# 3tastsp_v5_resistorcooldrive_battcheck.net
KiCad netlist of a schematic drawn in EAGLE
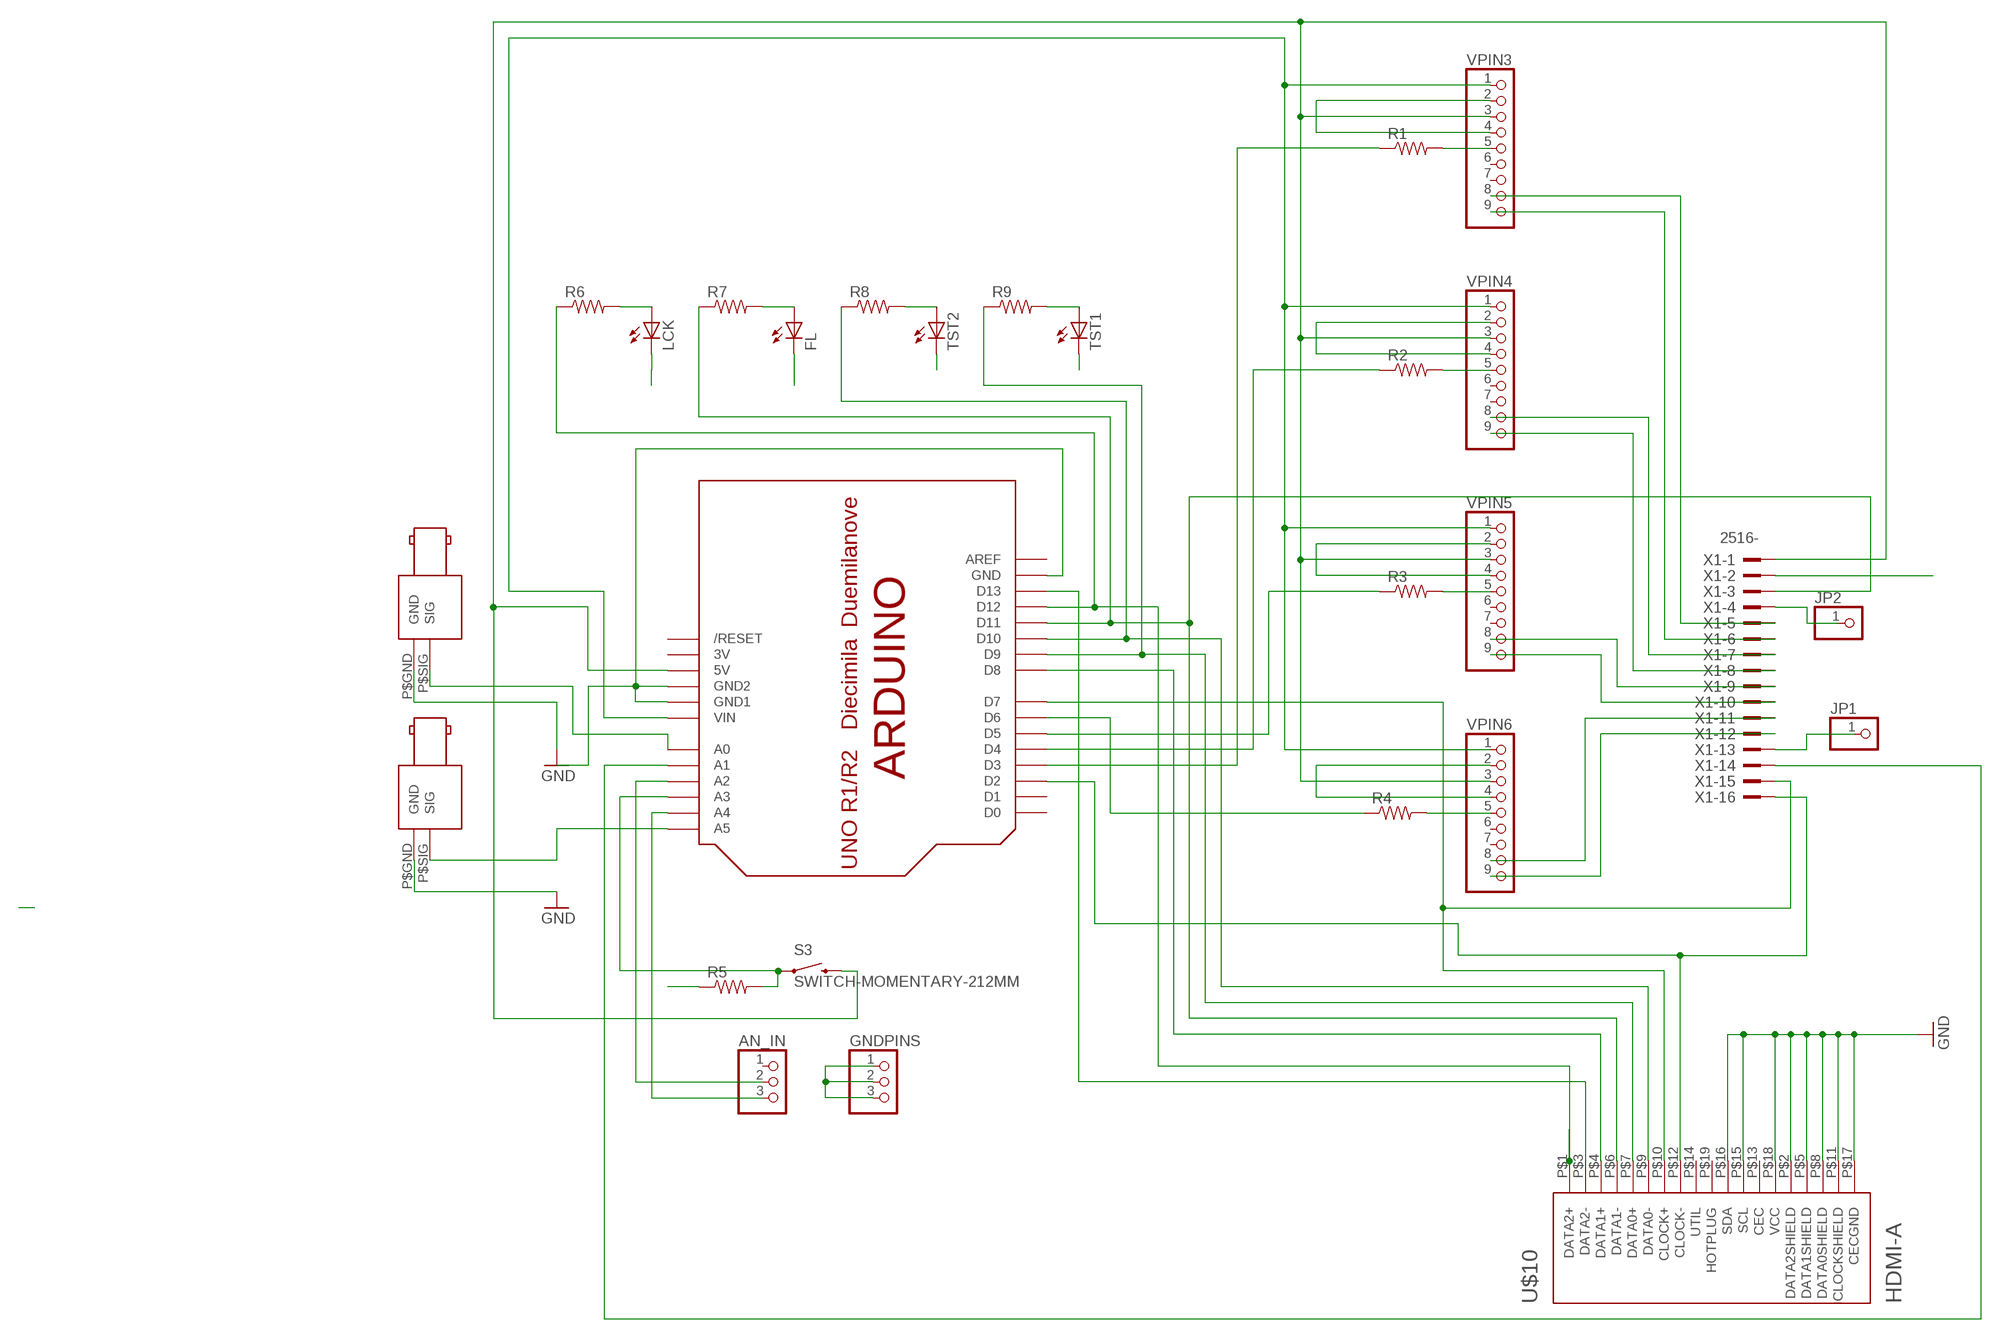
[diagram p0: schematic, sheet 1]

(export (version "E")
  (design (tool "Eeschema 10.0.6"))
  (components
    (comp (ref "AN_IN")
      (value "PINHD-1X3")
      (footprint "eagle-import:1X03")
      (libsource (lib "eagle-import") (part "PINHD-1X3"))
    )
    (comp (ref "FL")
      (value "LED5MM")
      (footprint "eagle-import:LED5MM")
      (libsource (lib "eagle-import") (part "LED5MM"))
    )
    (comp (ref "GNDPINS")
      (value "PINHD-1X3")
      (footprint "eagle-import:1X03")
      (libsource (lib "eagle-import") (part "PINHD-1X3"))
    )
    (comp (ref "JP1")
      (value "PINHD-1X1")
      (footprint "eagle-import:1X01")
      (libsource (lib "eagle-import") (part "PINHD-1X1"))
    )
    (comp (ref "JP2")
      (value "PINHD-1X1")
      (footprint "eagle-import:1X01")
      (libsource (lib "eagle-import") (part "PINHD-1X1"))
    )
    (comp (ref "LCK")
      (value "LED5MM")
      (footprint "eagle-import:LED5MM")
      (libsource (lib "eagle-import") (part "LED5MM"))
    )
    (comp (ref "LICKSIG")
      (value "BNC_RIGHT_ANGLE")
      (footprint "eagle-import:BNC_RIGHT_ANGLE")
      (libsource (lib "eagle-import") (part "BNC_RIGHT_ANGLE"))
    )
    (comp (ref "R1")
      (value "1KOHM-1/4W-1%(PTH)HORIZ-KIT")
      (footprint "eagle-import:AXIAL-0.3EZ")
      (libsource (lib "eagle-import") (part "1KOHM-1/4W-1%(PTH)HORIZ-KIT"))
    )
    (comp (ref "R2")
      (value "1KOHM-1/4W-1%(PTH)HORIZ-KIT")
      (footprint "eagle-import:AXIAL-0.3EZ")
      (libsource (lib "eagle-import") (part "1KOHM-1/4W-1%(PTH)HORIZ-KIT"))
    )
    (comp (ref "R3")
      (value "1KOHM-1/4W-1%(PTH)HORIZ-KIT")
      (footprint "eagle-import:AXIAL-0.3EZ")
      (libsource (lib "eagle-import") (part "1KOHM-1/4W-1%(PTH)HORIZ-KIT"))
    )
    (comp (ref "R4")
      (value "1KOHM-1/4W-1%(PTH)HORIZ-KIT")
      (footprint "eagle-import:AXIAL-0.3EZ")
      (libsource (lib "eagle-import") (part "1KOHM-1/4W-1%(PTH)HORIZ-KIT"))
    )
    (comp (ref "R5")
      (value "1KOHM-1/4W-1%(PTH)HORIZ-KIT")
      (footprint "eagle-import:AXIAL-0.3EZ")
      (libsource (lib "eagle-import") (part "1KOHM-1/4W-1%(PTH)HORIZ-KIT"))
    )
    (comp (ref "R6")
      (value "1KOHM-1/4W-1%(PTH)HORIZ-KIT")
      (footprint "eagle-import:AXIAL-0.3EZ")
      (libsource (lib "eagle-import") (part "1KOHM-1/4W-1%(PTH)HORIZ-KIT"))
    )
    (comp (ref "R7")
      (value "1KOHM-1/4W-1%(PTH)HORIZ-KIT")
      (footprint "eagle-import:AXIAL-0.3EZ")
      (libsource (lib "eagle-import") (part "1KOHM-1/4W-1%(PTH)HORIZ-KIT"))
    )
    (comp (ref "R8")
      (value "1KOHM-1/4W-1%(PTH)HORIZ-KIT")
      (footprint "eagle-import:AXIAL-0.3EZ")
      (libsource (lib "eagle-import") (part "1KOHM-1/4W-1%(PTH)HORIZ-KIT"))
    )
    (comp (ref "R9")
      (value "1KOHM-1/4W-1%(PTH)HORIZ-KIT")
      (footprint "eagle-import:AXIAL-0.3EZ")
      (libsource (lib "eagle-import") (part "1KOHM-1/4W-1%(PTH)HORIZ-KIT"))
    )
    (comp (ref "S3")
      (value "SWITCH-MOMENTARY-212MM")
      (footprint "eagle-import:TACTILE-PTH-12MM")
      (libsource (lib "eagle-import") (part "SWITCH-MOMENTARY-212MM"))
    )
    (comp (ref "TRIALSIG")
      (value "BNC_RIGHT_ANGLE")
      (footprint "eagle-import:BNC_RIGHT_ANGLE")
      (libsource (lib "eagle-import") (part "BNC_RIGHT_ANGLE"))
    )
    (comp (ref "TST1")
      (value "LED5MM")
      (footprint "eagle-import:LED5MM")
      (libsource (lib "eagle-import") (part "LED5MM"))
    )
    (comp (ref "TST2")
      (value "LED5MM")
      (footprint "eagle-import:LED5MM")
      (libsource (lib "eagle-import") (part "LED5MM"))
    )
    (comp (ref "U$1")
      (value "ARDUINO-NOHOLE")
      (footprint "eagle-import:ARDUINO-NOHOLE")
      (libsource (lib "eagle-import") (part "ARDUINO-NOHOLE"))
    )
    (comp (ref "U$10")
      (value "HDMI-A")
      (footprint "eagle-import:HDMI_A")
      (libsource (lib "eagle-import") (part "HDMI-A"))
    )
    (comp (ref "VPIN3")
      (value "PINHD-1X9")
      (footprint "eagle-import:1X09")
      (libsource (lib "eagle-import") (part "PINHD-1X9"))
    )
    (comp (ref "VPIN4")
      (value "PINHD-1X9")
      (footprint "eagle-import:1X09")
      (libsource (lib "eagle-import") (part "PINHD-1X9"))
    )
    (comp (ref "VPIN5")
      (value "PINHD-1X9")
      (footprint "eagle-import:1X09")
      (libsource (lib "eagle-import") (part "PINHD-1X9"))
    )
    (comp (ref "VPIN6")
      (value "PINHD-1X9")
      (footprint "eagle-import:1X09")
      (libsource (lib "eagle-import") (part "PINHD-1X9"))
    )
    (comp (ref "X1")
      (value "2516-")
      (footprint "eagle-import:PAK100_2500-16")
      (libsource (lib "eagle-import") (part "2516-"))
    )
  )
  (nets
    (net (code "1") (name "/3V") (class "Default")
      (node (ref "U$1") (pin "3V") (pinfunction "3V_3V") (pintype "power_in"))
    )
    (net (code "2") (name "GND") (class "Default")
      (node (ref "FL") (pin "K") (pinfunction "C_K") (pintype "passive"))
      (node (ref "GNDPINS") (pin "1") (pinfunction "1_1") (pintype "passive"))
      (node (ref "GNDPINS") (pin "2") (pinfunction "2_2") (pintype "passive"))
      (node (ref "GNDPINS") (pin "3") (pinfunction "3_3") (pintype "passive"))
      (node (ref "LCK") (pin "K") (pinfunction "C_K") (pintype "passive"))
      (node (ref "LICKSIG") (pin "P$GND") (pinfunction "GND_P$GND") (pintype "bidirectional"))
      (node (ref "R5") (pin "P$1") (pinfunction "1_P$1") (pintype "passive"))
      (node (ref "TRIALSIG") (pin "P$GND") (pinfunction "GND_P$GND") (pintype "bidirectional"))
      (node (ref "TST1") (pin "K") (pinfunction "C_K") (pintype "passive"))
      (node (ref "TST2") (pin "K") (pinfunction "C_K") (pintype "passive"))
      (node (ref "U$1") (pin "GND") (pinfunction "GND_GND") (pintype "power_in"))
      (node (ref "U$1") (pin "GND1") (pinfunction "GND1_GND1") (pintype "power_in"))
      (node (ref "U$1") (pin "GND2") (pinfunction "GND2_GND2") (pintype "power_in"))
      (node (ref "U$10") (pin "P$11") (pinfunction "CLOCKSHIELD_P$11") (pintype "bidirectional"))
      (node (ref "U$10") (pin "P$15") (pinfunction "SCL_P$15") (pintype "bidirectional"))
      (node (ref "U$10") (pin "P$16") (pinfunction "SDA_P$16") (pintype "bidirectional"))
      (node (ref "U$10") (pin "P$17") (pinfunction "CECGND_P$17") (pintype "bidirectional"))
      (node (ref "U$10") (pin "P$18") (pinfunction "VCC_P$18") (pintype "bidirectional"))
      (node (ref "U$10") (pin "P$2") (pinfunction "DATA2SHIELD_P$2") (pintype "bidirectional"))
      (node (ref "U$10") (pin "P$5") (pinfunction "DATA1SHIELD_P$5") (pintype "bidirectional"))
      (node (ref "U$10") (pin "P$8") (pinfunction "DATA0SHIELD_P$8") (pintype "bidirectional"))
      (node (ref "VPIN3") (pin "2") (pinfunction "2_2") (pintype "passive"))
      (node (ref "VPIN3") (pin "4") (pinfunction "4_4") (pintype "passive"))
      (node (ref "VPIN4") (pin "2") (pinfunction "2_2") (pintype "passive"))
      (node (ref "VPIN4") (pin "4") (pinfunction "4_4") (pintype "passive"))
      (node (ref "VPIN5") (pin "2") (pinfunction "2_2") (pintype "passive"))
      (node (ref "VPIN5") (pin "4") (pinfunction "4_4") (pintype "passive"))
      (node (ref "VPIN6") (pin "2") (pinfunction "2_2") (pintype "passive"))
      (node (ref "VPIN6") (pin "4") (pinfunction "4_4") (pintype "passive"))
      (node (ref "X1") (pin "2") (pinfunction "KL_2") (pintype "passive"))
    )
    (net (code "3") (name "Net-(AN_IN-Pad2)") (class "Default")
      (node (ref "AN_IN") (pin "2") (pinfunction "2_2") (pintype "passive"))
      (node (ref "U$1") (pin "A2") (pinfunction "A2_A2") (pintype "bidirectional"))
    )
    (net (code "4") (name "Net-(AN_IN-Pad3)") (class "Default")
      (node (ref "AN_IN") (pin "3") (pinfunction "3_3") (pintype "passive"))
      (node (ref "U$1") (pin "A4") (pinfunction "A4_A4") (pintype "bidirectional"))
    )
    (net (code "5") (name "Net-(LICKSIG-SIG)") (class "Default")
      (node (ref "LICKSIG") (pin "P$SIG") (pinfunction "SIG_P$SIG") (pintype "bidirectional"))
      (node (ref "U$1") (pin "A0") (pinfunction "A0_A0") (pintype "bidirectional"))
    )
    (net (code "6") (name "Net-(R1-1)") (class "Default")
      (node (ref "R1") (pin "P$1") (pinfunction "1_P$1") (pintype "passive"))
      (node (ref "U$1") (pin "D3") (pinfunction "D3_D3") (pintype "bidirectional"))
    )
    (net (code "7") (name "Net-(R1-2)") (class "Default")
      (node (ref "R1") (pin "P$2") (pinfunction "2_P$2") (pintype "passive"))
      (node (ref "VPIN3") (pin "5") (pinfunction "5_5") (pintype "passive"))
    )
    (net (code "8") (name "Net-(R2-1)") (class "Default")
      (node (ref "R2") (pin "P$1") (pinfunction "1_P$1") (pintype "passive"))
      (node (ref "U$1") (pin "D4") (pinfunction "D4_D4") (pintype "bidirectional"))
    )
    (net (code "9") (name "Net-(R2-2)") (class "Default")
      (node (ref "R2") (pin "P$2") (pinfunction "2_P$2") (pintype "passive"))
      (node (ref "VPIN4") (pin "5") (pinfunction "5_5") (pintype "passive"))
    )
    (net (code "10") (name "Net-(R3-1)") (class "Default")
      (node (ref "R3") (pin "P$1") (pinfunction "1_P$1") (pintype "passive"))
      (node (ref "U$1") (pin "D5") (pinfunction "D5_D5") (pintype "bidirectional"))
    )
    (net (code "11") (name "Net-(R3-2)") (class "Default")
      (node (ref "R3") (pin "P$2") (pinfunction "2_P$2") (pintype "passive"))
      (node (ref "VPIN5") (pin "5") (pinfunction "5_5") (pintype "passive"))
    )
    (net (code "12") (name "Net-(R4-1)") (class "Default")
      (node (ref "R4") (pin "P$1") (pinfunction "1_P$1") (pintype "passive"))
      (node (ref "U$1") (pin "D6") (pinfunction "D6_D6") (pintype "bidirectional"))
    )
    (net (code "13") (name "Net-(R4-2)") (class "Default")
      (node (ref "R4") (pin "P$2") (pinfunction "2_P$2") (pintype "passive"))
      (node (ref "VPIN6") (pin "5") (pinfunction "5_5") (pintype "passive"))
    )
    (net (code "14") (name "Net-(R5-2)") (class "Default")
      (node (ref "R5") (pin "P$2") (pinfunction "2_P$2") (pintype "passive"))
      (node (ref "S3") (pin "1") (pinfunction "1_1") (pintype "passive"))
      (node (ref "U$1") (pin "A3") (pinfunction "A3_A3") (pintype "bidirectional"))
    )
    (net (code "15") (name "Net-(R6-1)") (class "Default")
      (node (ref "R6") (pin "P$1") (pinfunction "1_P$1") (pintype "passive"))
      (node (ref "U$1") (pin "D12") (pinfunction "D12_D12") (pintype "bidirectional"))
      (node (ref "U$10") (pin "P$1") (pinfunction "DATA2+_P$1") (pintype "bidirectional"))
    )
    (net (code "16") (name "Net-(R6-2)") (class "Default")
      (node (ref "LCK") (pin "A") (pinfunction "A_A") (pintype "passive"))
      (node (ref "R6") (pin "P$2") (pinfunction "2_P$2") (pintype "passive"))
    )
    (net (code "17") (name "Net-(R7-1)") (class "Default")
      (node (ref "R7") (pin "P$1") (pinfunction "1_P$1") (pintype "passive"))
      (node (ref "U$1") (pin "D11") (pinfunction "D11_D11") (pintype "bidirectional"))
      (node (ref "U$10") (pin "P$6") (pinfunction "DATA1-_P$6") (pintype "bidirectional"))
      (node (ref "X1") (pin "3") (pinfunction "KL_3") (pintype "passive"))
    )
    (net (code "18") (name "Net-(R7-2)") (class "Default")
      (node (ref "FL") (pin "A") (pinfunction "A_A") (pintype "passive"))
      (node (ref "R7") (pin "P$2") (pinfunction "2_P$2") (pintype "passive"))
    )
    (net (code "19") (name "Net-(R8-1)") (class "Default")
      (node (ref "R8") (pin "P$1") (pinfunction "1_P$1") (pintype "passive"))
      (node (ref "U$1") (pin "D10") (pinfunction "D10_D10") (pintype "bidirectional"))
      (node (ref "U$10") (pin "P$9") (pinfunction "DATA0-_P$9") (pintype "bidirectional"))
    )
    (net (code "20") (name "Net-(R8-2)") (class "Default")
      (node (ref "R8") (pin "P$2") (pinfunction "2_P$2") (pintype "passive"))
      (node (ref "TST2") (pin "A") (pinfunction "A_A") (pintype "passive"))
    )
    (net (code "21") (name "Net-(R9-1)") (class "Default")
      (node (ref "R9") (pin "P$1") (pinfunction "1_P$1") (pintype "passive"))
      (node (ref "U$1") (pin "D9") (pinfunction "D9_D9") (pintype "bidirectional"))
      (node (ref "U$10") (pin "P$7") (pinfunction "DATA0+_P$7") (pintype "bidirectional"))
    )
    (net (code "22") (name "Net-(R9-2)") (class "Default")
      (node (ref "R9") (pin "P$2") (pinfunction "2_P$2") (pintype "passive"))
      (node (ref "TST1") (pin "A") (pinfunction "A_A") (pintype "passive"))
    )
    (net (code "23") (name "Net-(S3-2)") (class "Default")
      (node (ref "S3") (pin "3") (pinfunction "2_3") (pintype "passive"))
      (node (ref "U$1") (pin "5V") (pinfunction "5V_5V") (pintype "power_in"))
      (node (ref "VPIN3") (pin "3") (pinfunction "3_3") (pintype "passive"))
      (node (ref "VPIN4") (pin "3") (pinfunction "3_3") (pintype "passive"))
      (node (ref "VPIN5") (pin "3") (pinfunction "3_3") (pintype "passive"))
      (node (ref "VPIN6") (pin "3") (pinfunction "3_3") (pintype "passive"))
      (node (ref "X1") (pin "1") (pinfunction "KL_1") (pintype "passive"))
    )
    (net (code "24") (name "Net-(TRIALSIG-SIG)") (class "Default")
      (node (ref "TRIALSIG") (pin "P$SIG") (pinfunction "SIG_P$SIG") (pintype "bidirectional"))
      (node (ref "U$1") (pin "A5") (pinfunction "A5_A5") (pintype "bidirectional"))
    )
    (net (code "25") (name "Net-(U$1-PadVIN)") (class "Default")
      (node (ref "U$1") (pin "VIN") (pinfunction "VIN_VIN") (pintype "power_in"))
      (node (ref "VPIN3") (pin "1") (pinfunction "1_1") (pintype "passive"))
      (node (ref "VPIN4") (pin "1") (pinfunction "1_1") (pintype "passive"))
      (node (ref "VPIN5") (pin "1") (pinfunction "1_1") (pintype "passive"))
      (node (ref "VPIN6") (pin "1") (pinfunction "1_1") (pintype "passive"))
    )
    (net (code "26") (name "Net-(U$10-CLOCK+)") (class "Default")
      (node (ref "U$1") (pin "D7") (pinfunction "D7_D7") (pintype "bidirectional"))
      (node (ref "U$10") (pin "P$10") (pinfunction "CLOCK+_P$10") (pintype "bidirectional"))
      (node (ref "X1") (pin "15") (pinfunction "KL_15") (pintype "passive"))
    )
    (net (code "27") (name "Net-(U$10-CLOCK-)") (class "Default")
      (node (ref "U$1") (pin "D2") (pinfunction "D2_D2") (pintype "bidirectional"))
      (node (ref "U$10") (pin "P$12") (pinfunction "CLOCK-_P$12") (pintype "bidirectional"))
      (node (ref "X1") (pin "16") (pinfunction "KL_16") (pintype "passive"))
    )
    (net (code "28") (name "Net-(U$10-DATA1+)") (class "Default")
      (node (ref "U$1") (pin "D8") (pinfunction "D8_D8") (pintype "bidirectional"))
      (node (ref "U$10") (pin "P$4") (pinfunction "DATA1+_P$4") (pintype "bidirectional"))
    )
    (net (code "29") (name "Net-(U$10-DATA2-)") (class "Default")
      (node (ref "U$1") (pin "D13") (pinfunction "D13_D13") (pintype "bidirectional"))
      (node (ref "U$10") (pin "P$3") (pinfunction "DATA2-_P$3") (pintype "bidirectional"))
    )
    (net (code "30") (name "Net-(X1B-KL)") (class "Default")
      (node (ref "VPIN5") (pin "9") (pinfunction "9_9") (pintype "passive"))
      (node (ref "X1") (pin "10") (pinfunction "KL_10") (pintype "passive"))
    )
    (net (code "31") (name "Net-(X1C-KL)") (class "Default")
      (node (ref "VPIN6") (pin "8") (pinfunction "8_8") (pintype "passive"))
      (node (ref "X1") (pin "11") (pinfunction "KL_11") (pintype "passive"))
    )
    (net (code "32") (name "Net-(X1D-KL)") (class "Default")
      (node (ref "VPIN6") (pin "9") (pinfunction "9_9") (pintype "passive"))
      (node (ref "X1") (pin "12") (pinfunction "KL_12") (pintype "passive"))
    )
    (net (code "33") (name "Net-(X1E-KL)") (class "Default")
      (node (ref "JP1") (pin "1") (pinfunction "1_1") (pintype "passive"))
      (node (ref "X1") (pin "13") (pinfunction "KL_13") (pintype "passive"))
    )
    (net (code "34") (name "Net-(X1F-KL)") (class "Default")
      (node (ref "U$1") (pin "A1") (pinfunction "A1_A1") (pintype "bidirectional"))
      (node (ref "X1") (pin "14") (pinfunction "KL_14") (pintype "passive"))
    )
    (net (code "35") (name "Net-(X1K-KL)") (class "Default")
      (node (ref "JP2") (pin "1") (pinfunction "1_1") (pintype "passive"))
      (node (ref "X1") (pin "4") (pinfunction "KL_4") (pintype "passive"))
    )
    (net (code "36") (name "Net-(X1L-KL)") (class "Default")
      (node (ref "VPIN3") (pin "8") (pinfunction "8_8") (pintype "passive"))
      (node (ref "X1") (pin "5") (pinfunction "KL_5") (pintype "passive"))
    )
    (net (code "37") (name "Net-(X1M-KL)") (class "Default")
      (node (ref "VPIN3") (pin "9") (pinfunction "9_9") (pintype "passive"))
      (node (ref "X1") (pin "6") (pinfunction "KL_6") (pintype "passive"))
    )
    (net (code "38") (name "Net-(X1N-KL)") (class "Default")
      (node (ref "VPIN4") (pin "8") (pinfunction "8_8") (pintype "passive"))
      (node (ref "X1") (pin "7") (pinfunction "KL_7") (pintype "passive"))
    )
    (net (code "39") (name "Net-(X1O-KL)") (class "Default")
      (node (ref "VPIN4") (pin "9") (pinfunction "9_9") (pintype "passive"))
      (node (ref "X1") (pin "8") (pinfunction "KL_8") (pintype "passive"))
    )
    (net (code "40") (name "Net-(X1P-KL)") (class "Default")
      (node (ref "VPIN5") (pin "8") (pinfunction "8_8") (pintype "passive"))
      (node (ref "X1") (pin "9") (pinfunction "KL_9") (pintype "passive"))
    )
    (net (code "41") (name "unconnected-(AN_IN-Pad1)") (class "Default")
      (node (ref "AN_IN") (pin "1") (pinfunction "1_1") (pintype "passive"))
    )
    (net (code "42") (name "unconnected-(U$1-PadAREF)") (class "Default")
      (node (ref "U$1") (pin "AREF") (pinfunction "AREF_AREF") (pintype "bidirectional"))
    )
    (net (code "43") (name "unconnected-(U$1-PadD0)") (class "Default")
      (node (ref "U$1") (pin "D0") (pinfunction "D0_D0") (pintype "bidirectional"))
    )
    (net (code "44") (name "unconnected-(U$1-PadD1)") (class "Default")
      (node (ref "U$1") (pin "D1") (pinfunction "D1_D1") (pintype "bidirectional"))
    )
    (net (code "45") (name "unconnected-(U$1-{slash}RESET-PadRESET)") (class "Default")
      (node (ref "U$1") (pin "RESET") (pinfunction "/RESET_RESET") (pintype "bidirectional"))
    )
    (net (code "46") (name "unconnected-(U$10-CEC-PadP$13)") (class "Default")
      (node (ref "U$10") (pin "P$13") (pinfunction "CEC_P$13") (pintype "bidirectional"))
    )
    (net (code "47") (name "unconnected-(U$10-HOTPLUG-PadP$19)") (class "Default")
      (node (ref "U$10") (pin "P$19") (pinfunction "HOTPLUG_P$19") (pintype "bidirectional"))
    )
    (net (code "48") (name "unconnected-(U$10-UTIL-PadP$14)") (class "Default")
      (node (ref "U$10") (pin "P$14") (pinfunction "UTIL_P$14") (pintype "bidirectional"))
    )
    (net (code "49") (name "unconnected-(VPIN3-Pad6)") (class "Default")
      (node (ref "VPIN3") (pin "6") (pinfunction "6_6") (pintype "passive"))
    )
    (net (code "50") (name "unconnected-(VPIN3-Pad7)") (class "Default")
      (node (ref "VPIN3") (pin "7") (pinfunction "7_7") (pintype "passive"))
    )
    (net (code "51") (name "unconnected-(VPIN4-Pad6)") (class "Default")
      (node (ref "VPIN4") (pin "6") (pinfunction "6_6") (pintype "passive"))
    )
    (net (code "52") (name "unconnected-(VPIN4-Pad7)") (class "Default")
      (node (ref "VPIN4") (pin "7") (pinfunction "7_7") (pintype "passive"))
    )
    (net (code "53") (name "unconnected-(VPIN5-Pad6)") (class "Default")
      (node (ref "VPIN5") (pin "6") (pinfunction "6_6") (pintype "passive"))
    )
    (net (code "54") (name "unconnected-(VPIN5-Pad7)") (class "Default")
      (node (ref "VPIN5") (pin "7") (pinfunction "7_7") (pintype "passive"))
    )
    (net (code "55") (name "unconnected-(VPIN6-Pad6)") (class "Default")
      (node (ref "VPIN6") (pin "6") (pinfunction "6_6") (pintype "passive"))
    )
    (net (code "56") (name "unconnected-(VPIN6-Pad7)") (class "Default")
      (node (ref "VPIN6") (pin "7") (pinfunction "7_7") (pintype "passive"))
    )
  )
)
